# MaxBuckSch.net
KiCad netlist of a schematic drawn in EAGLE
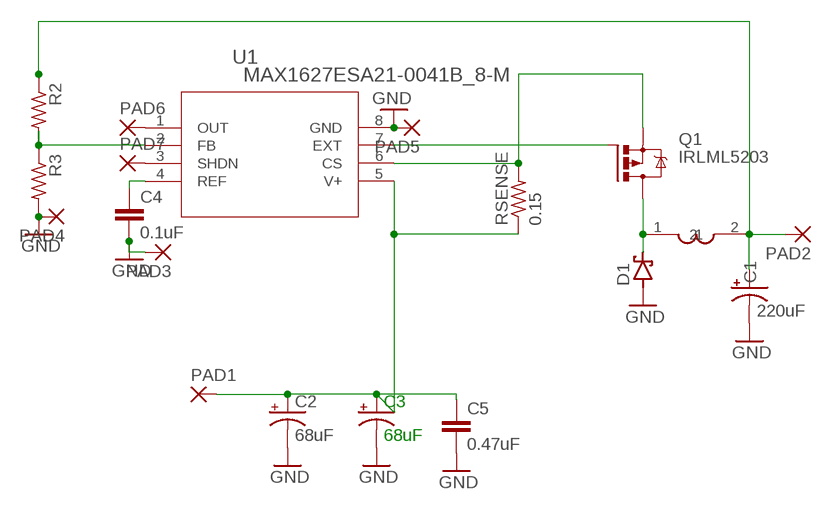
[diagram p0: schematic, sheet 1]

(export (version "E")
  (design (tool "Eeschema 10.0.6"))
  (components
    (comp (ref "C1")
      (value "220uF")
      (footprint "eagle-import:D_7343-31W")
      (libsource (lib "eagle-import") (part "CPOL-USD/7343-31W"))
    )
    (comp (ref "C2")
      (value "68uF")
      (footprint "eagle-import:D_7343-31W")
      (libsource (lib "eagle-import") (part "CPOL-USD/7343-31W"))
    )
    (comp (ref "C3")
      (value "68uF")
      (footprint "eagle-import:D_7343-31W")
      (libsource (lib "eagle-import") (part "CPOL-USD/7343-31W"))
    )
    (comp (ref "C4")
      (value "0.1uF")
      (footprint "eagle-import:C0805K")
      (libsource (lib "eagle-import") (part "C-EUC0805K"))
    )
    (comp (ref "C5")
      (value "0.47uF")
      (footprint "eagle-import:C0805K")
      (libsource (lib "eagle-import") (part "C-EUC0805K"))
    )
    (comp (ref "D1")
      (value "SCHOTTKY-DIODESMC")
      (footprint "eagle-import:SMC")
      (libsource (lib "eagle-import") (part "SCHOTTKY-DIODESMC"))
    )
    (comp (ref "PAD1")
      (value "2,15/1,0")
      (footprint "eagle-import:2,15_1,0")
      (libsource (lib "eagle-import") (part "2,15/1,0"))
    )
    (comp (ref "PAD2")
      (value "2,15/1,0")
      (footprint "eagle-import:2,15_1,0")
      (libsource (lib "eagle-import") (part "2,15/1,0"))
    )
    (comp (ref "PAD3")
      (value "2,15/1,0")
      (footprint "eagle-import:2,15_1,0")
      (libsource (lib "eagle-import") (part "2,15/1,0"))
    )
    (comp (ref "PAD4")
      (value "2,15/1,0")
      (footprint "eagle-import:2,15_1,0")
      (libsource (lib "eagle-import") (part "2,15/1,0"))
    )
    (comp (ref "PAD5")
      (value "2,15/1,0")
      (footprint "eagle-import:2,15_1,0")
      (libsource (lib "eagle-import") (part "2,15/1,0"))
    )
    (comp (ref "PAD6")
      (value "2,15/1,0")
      (footprint "eagle-import:2,15_1,0")
      (libsource (lib "eagle-import") (part "2,15/1,0"))
    )
    (comp (ref "PAD7")
      (value "2,15/1,0")
      (footprint "eagle-import:2,15_1,0")
      (libsource (lib "eagle-import") (part "2,15/1,0"))
    )
    (comp (ref "Q1")
      (value "IRLML5203")
      (footprint "eagle-import:MICRO3")
      (libsource (lib "eagle-import") (part "IRLML5203"))
    )
    (comp (ref "R2")
      (value "R-US_R0805W")
      (footprint "eagle-import:R0805W")
      (libsource (lib "eagle-import") (part "R-US_R0805W"))
    )
    (comp (ref "R3")
      (value "R-US_R0805W")
      (footprint "eagle-import:R0805W")
      (libsource (lib "eagle-import") (part "R-US_R0805W"))
    )
    (comp (ref "RSENSE")
      (value "0.15")
      (footprint "eagle-import:R0805W")
      (libsource (lib "eagle-import") (part "R-US_R0805W"))
    )
    (comp (ref "U$1")
      (value "EE348")
      (footprint "eagle-import:INDUCTOR")
      (libsource (lib "eagle-import") (part "EE348"))
    )
    (comp (ref "U1")
      (value "MAX1627ESA21-0041B_8-M")
      (footprint "eagle-import:21-0041B_8-M")
      (fields (field (name "MANUFACTURER_PART_NUMBER") "max1627esa"))
      (libsource (lib "eagle-import") (part "MAX1627ESA21-0041B_8-M"))
    )
  )
  (nets
    (net (code "1") (name "GND") (class "Default")
      (node (ref "C1") (pin "-") (pinfunction "-_-") (pintype "passive"))
      (node (ref "C2") (pin "-") (pinfunction "-_-") (pintype "passive"))
      (node (ref "C3") (pin "-") (pinfunction "-_-") (pintype "passive"))
      (node (ref "C4") (pin "2") (pinfunction "2_2") (pintype "passive"))
      (node (ref "C5") (pin "2") (pinfunction "2_2") (pintype "passive"))
      (node (ref "D1") (pin "A") (pinfunction "A_A") (pintype "passive"))
      (node (ref "PAD3") (pin "1") (pinfunction "P_1") (pintype "passive"))
      (node (ref "PAD4") (pin "1") (pinfunction "P_1") (pintype "passive"))
      (node (ref "PAD5") (pin "1") (pinfunction "P_1") (pintype "passive"))
      (node (ref "R3") (pin "2") (pinfunction "2_2") (pintype "passive"))
      (node (ref "U1") (pin "8") (pinfunction "GND_8") (pintype "power_in"))
    )
    (net (code "2") (name "Net-(PAD1-P)") (class "Default")
      (node (ref "C2") (pin "+") (pinfunction "+_+") (pintype "passive"))
      (node (ref "C3") (pin "+") (pinfunction "+_+") (pintype "passive"))
      (node (ref "C5") (pin "1") (pinfunction "1_1") (pintype "passive"))
      (node (ref "PAD1") (pin "1") (pinfunction "P_1") (pintype "passive"))
      (node (ref "RSENSE") (pin "1") (pinfunction "1_1") (pintype "passive"))
      (node (ref "U1") (pin "5") (pinfunction "V+_5") (pintype "power_in"))
    )
    (net (code "3") (name "Net-(PAD2-P)") (class "Default")
      (node (ref "C1") (pin "+") (pinfunction "+_+") (pintype "passive"))
      (node (ref "PAD2") (pin "1") (pinfunction "P_1") (pintype "passive"))
      (node (ref "R2") (pin "1") (pinfunction "1_1") (pintype "passive"))
      (node (ref "U$1") (pin "2") (pinfunction "2_2") (pintype "bidirectional"))
    )
    (net (code "4") (name "Net-(PAD6-P)") (class "Default")
      (node (ref "PAD6") (pin "1") (pinfunction "P_1") (pintype "passive"))
      (node (ref "U1") (pin "1") (pinfunction "OUT_1") (pintype "input"))
    )
    (net (code "5") (name "Net-(PAD7-P)") (class "Default")
      (node (ref "PAD7") (pin "1") (pinfunction "P_1") (pintype "passive"))
      (node (ref "U1") (pin "3") (pinfunction "SHDN_3") (pintype "input"))
    )
    (net (code "6") (name "Net-(Q1-D)") (class "Default")
      (node (ref "D1") (pin "C") (pinfunction "C_C") (pintype "passive"))
      (node (ref "Q1") (pin "3") (pinfunction "D_3") (pintype "passive"))
      (node (ref "U$1") (pin "1") (pinfunction "1_1") (pintype "bidirectional"))
    )
    (net (code "7") (name "Net-(Q1-G)") (class "Default")
      (node (ref "Q1") (pin "1") (pinfunction "G_1") (pintype "passive"))
      (node (ref "U1") (pin "7") (pinfunction "EXT_7") (pintype "passive"))
    )
    (net (code "8") (name "Net-(Q1-S)") (class "Default")
      (node (ref "Q1") (pin "2") (pinfunction "S_2") (pintype "passive"))
      (node (ref "RSENSE") (pin "2") (pinfunction "2_2") (pintype "passive"))
      (node (ref "U1") (pin "6") (pinfunction "CS_6") (pintype "input"))
    )
    (net (code "9") (name "Net-(U1-FB)") (class "Default")
      (node (ref "R2") (pin "2") (pinfunction "2_2") (pintype "passive"))
      (node (ref "R3") (pin "1") (pinfunction "1_1") (pintype "passive"))
      (node (ref "U1") (pin "2") (pinfunction "FB_2") (pintype "input"))
    )
    (net (code "10") (name "Net-(U1-REF)") (class "Default")
      (node (ref "C4") (pin "1") (pinfunction "1_1") (pintype "passive"))
      (node (ref "U1") (pin "4") (pinfunction "REF_4") (pintype "output"))
    )
  )
)
